# streams_v02_bargraph.net
KiCad netlist of a schematic drawn in EAGLE
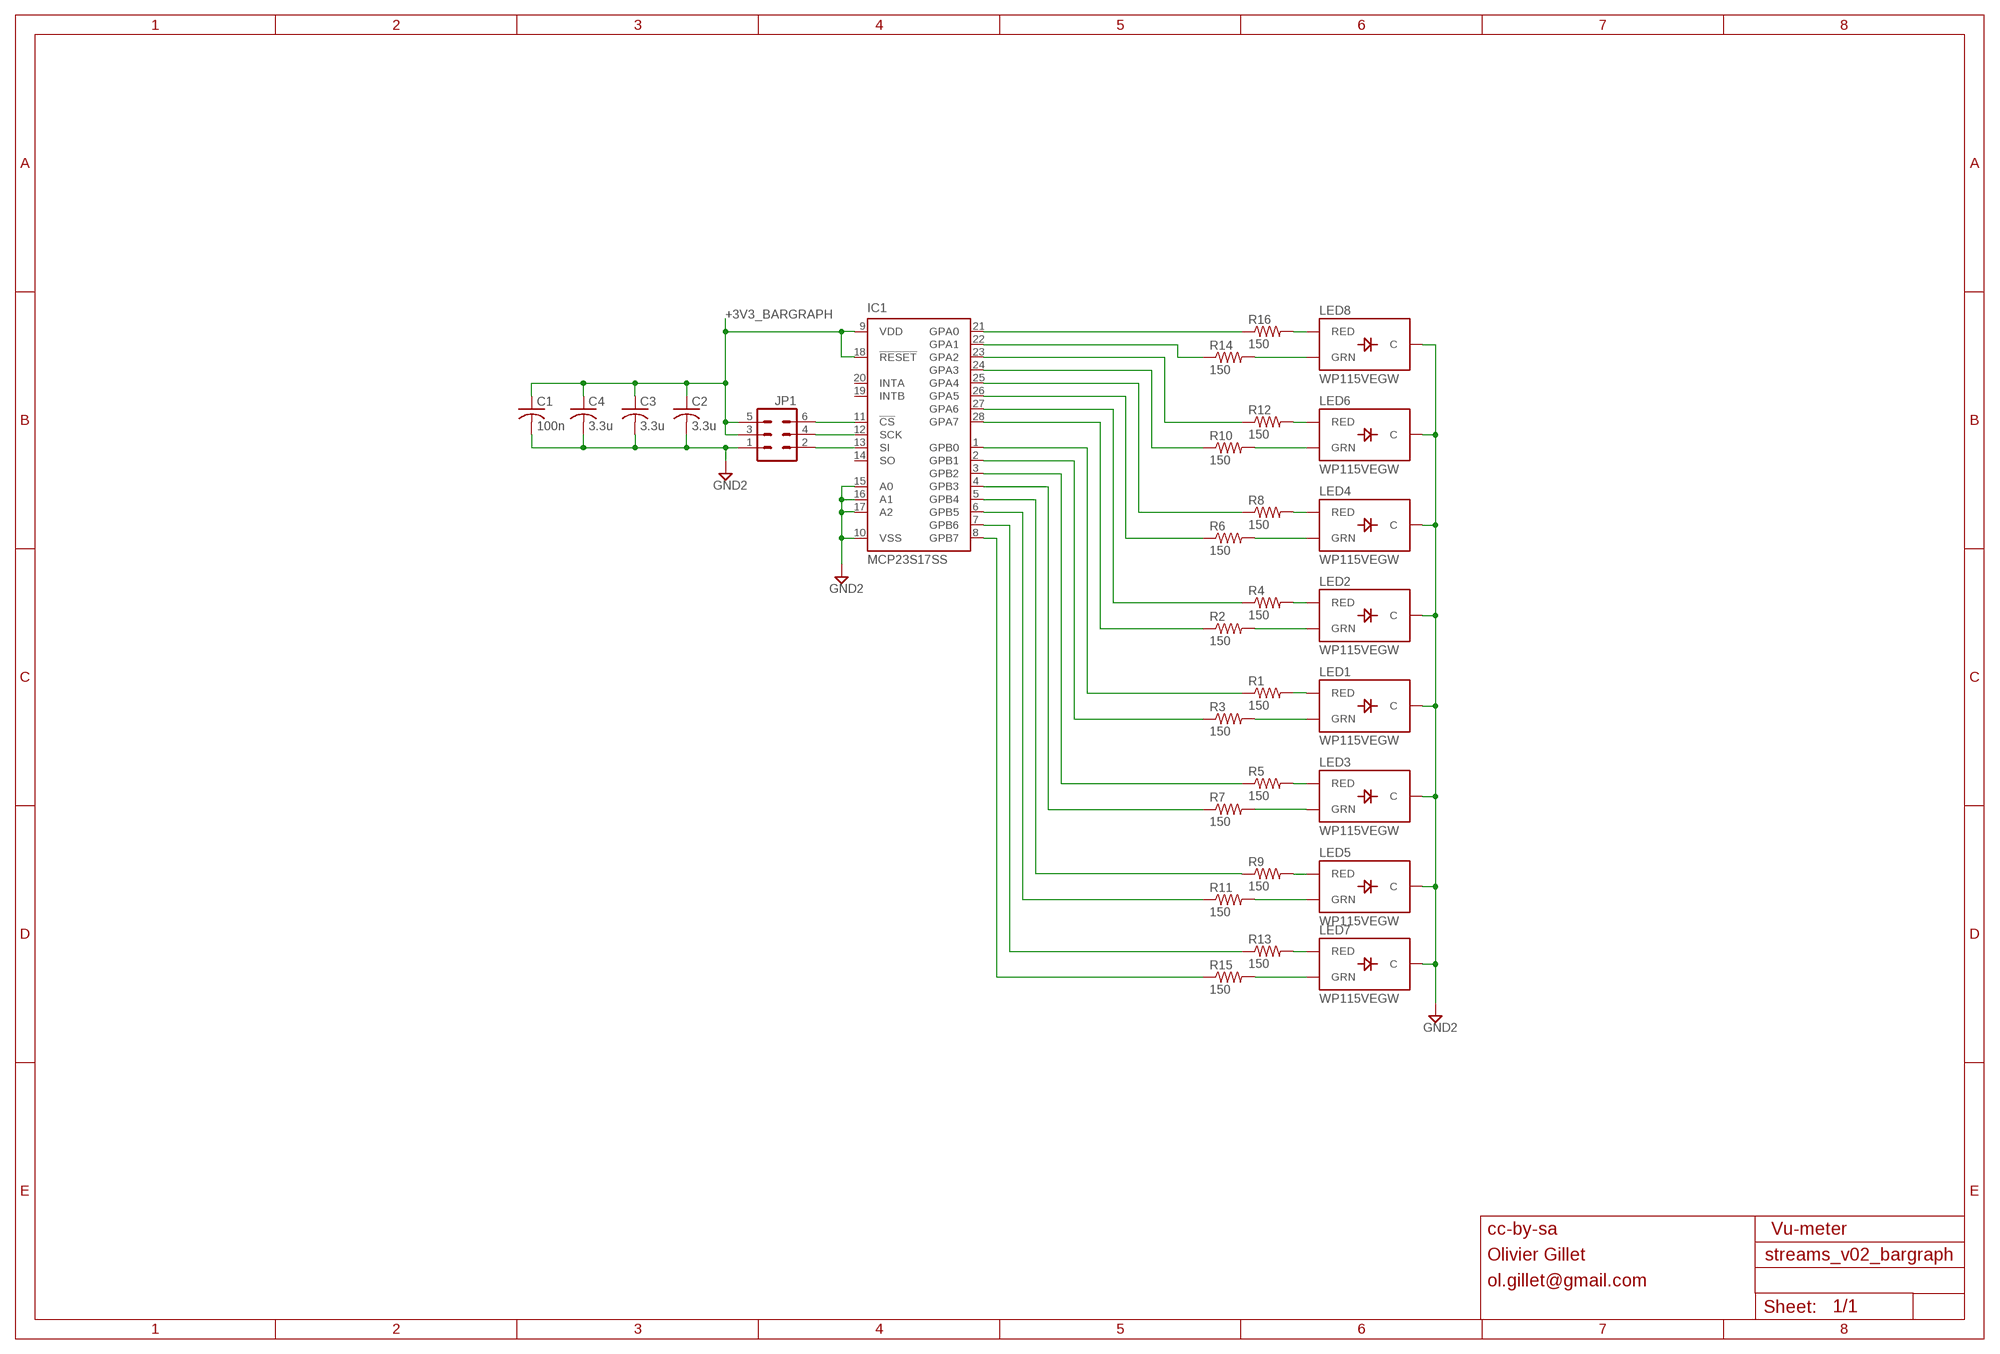
[diagram p0: schematic, sheet 1]

(export (version "E")
  (design (tool "Eeschema 10.0.6"))
  (components
    (comp (ref "C1")
      (value "100n")
      (footprint "eagle-import:C0603")
      (libsource (lib "eagle-import") (part "C-USC0603"))
    )
    (comp (ref "C2")
      (value "3.3u")
      (footprint "eagle-import:C0603")
      (libsource (lib "eagle-import") (part "C-USC0603"))
    )
    (comp (ref "C3")
      (value "3.3u")
      (footprint "eagle-import:C0603")
      (libsource (lib "eagle-import") (part "C-USC0603"))
    )
    (comp (ref "C4")
      (value "3.3u")
      (footprint "eagle-import:C0603")
      (libsource (lib "eagle-import") (part "C-USC0603"))
    )
    (comp (ref "IC1")
      (value "MCP23S17SS")
      (footprint "eagle-import:SSOP28")
      (libsource (lib "eagle-import") (part "MCP23S17SS"))
    )
    (comp (ref "JP1")
      (value "M03X2")
      (footprint "eagle-import:2X3")
      (libsource (lib "eagle-import") (part "M03X2"))
    )
    (comp (ref "LED1")
      (value "WP115VEGW")
      (footprint "eagle-import:LED-BICOLOR-THROUGHHOLE")
      (libsource (lib "eagle-import") (part "LED-BICOLOR-THROUGHHOLE"))
    )
    (comp (ref "LED2")
      (value "WP115VEGW")
      (footprint "eagle-import:LED-BICOLOR-THROUGHHOLE")
      (libsource (lib "eagle-import") (part "LED-BICOLOR-THROUGHHOLE"))
    )
    (comp (ref "LED3")
      (value "WP115VEGW")
      (footprint "eagle-import:LED-BICOLOR-THROUGHHOLE")
      (libsource (lib "eagle-import") (part "LED-BICOLOR-THROUGHHOLE"))
    )
    (comp (ref "LED4")
      (value "WP115VEGW")
      (footprint "eagle-import:LED-BICOLOR-THROUGHHOLE")
      (libsource (lib "eagle-import") (part "LED-BICOLOR-THROUGHHOLE"))
    )
    (comp (ref "LED5")
      (value "WP115VEGW")
      (footprint "eagle-import:LED-BICOLOR-THROUGHHOLE")
      (libsource (lib "eagle-import") (part "LED-BICOLOR-THROUGHHOLE"))
    )
    (comp (ref "LED6")
      (value "WP115VEGW")
      (footprint "eagle-import:LED-BICOLOR-THROUGHHOLE")
      (libsource (lib "eagle-import") (part "LED-BICOLOR-THROUGHHOLE"))
    )
    (comp (ref "LED7")
      (value "WP115VEGW")
      (footprint "eagle-import:LED-BICOLOR-THROUGHHOLE")
      (libsource (lib "eagle-import") (part "LED-BICOLOR-THROUGHHOLE"))
    )
    (comp (ref "LED8")
      (value "WP115VEGW")
      (footprint "eagle-import:LED-BICOLOR-THROUGHHOLE")
      (libsource (lib "eagle-import") (part "LED-BICOLOR-THROUGHHOLE"))
    )
    (comp (ref "R1")
      (value "150")
      (footprint "eagle-import:R0603")
      (libsource (lib "eagle-import") (part "R-US_R0603"))
    )
    (comp (ref "R2")
      (value "150")
      (footprint "eagle-import:R0603")
      (libsource (lib "eagle-import") (part "R-US_R0603"))
    )
    (comp (ref "R3")
      (value "150")
      (footprint "eagle-import:R0603")
      (libsource (lib "eagle-import") (part "R-US_R0603"))
    )
    (comp (ref "R4")
      (value "150")
      (footprint "eagle-import:R0603")
      (libsource (lib "eagle-import") (part "R-US_R0603"))
    )
    (comp (ref "R5")
      (value "150")
      (footprint "eagle-import:R0603")
      (libsource (lib "eagle-import") (part "R-US_R0603"))
    )
    (comp (ref "R6")
      (value "150")
      (footprint "eagle-import:R0603")
      (libsource (lib "eagle-import") (part "R-US_R0603"))
    )
    (comp (ref "R7")
      (value "150")
      (footprint "eagle-import:R0603")
      (libsource (lib "eagle-import") (part "R-US_R0603"))
    )
    (comp (ref "R8")
      (value "150")
      (footprint "eagle-import:R0603")
      (libsource (lib "eagle-import") (part "R-US_R0603"))
    )
    (comp (ref "R9")
      (value "150")
      (footprint "eagle-import:R0603")
      (libsource (lib "eagle-import") (part "R-US_R0603"))
    )
    (comp (ref "R10")
      (value "150")
      (footprint "eagle-import:R0603")
      (libsource (lib "eagle-import") (part "R-US_R0603"))
    )
    (comp (ref "R11")
      (value "150")
      (footprint "eagle-import:R0603")
      (libsource (lib "eagle-import") (part "R-US_R0603"))
    )
    (comp (ref "R12")
      (value "150")
      (footprint "eagle-import:R0603")
      (libsource (lib "eagle-import") (part "R-US_R0603"))
    )
    (comp (ref "R13")
      (value "150")
      (footprint "eagle-import:R0603")
      (libsource (lib "eagle-import") (part "R-US_R0603"))
    )
    (comp (ref "R14")
      (value "150")
      (footprint "eagle-import:R0603")
      (libsource (lib "eagle-import") (part "R-US_R0603"))
    )
    (comp (ref "R15")
      (value "150")
      (footprint "eagle-import:R0603")
      (libsource (lib "eagle-import") (part "R-US_R0603"))
    )
    (comp (ref "R16")
      (value "150")
      (footprint "eagle-import:R0603")
      (libsource (lib "eagle-import") (part "R-US_R0603"))
    )
  )
  (nets
    (net (code "1") (name "/+3V3_BARGRAPH") (class "Default")
      (node (ref "C1") (pin "1") (pinfunction "1_1") (pintype "passive"))
      (node (ref "C2") (pin "1") (pinfunction "1_1") (pintype "passive"))
      (node (ref "C3") (pin "1") (pinfunction "1_1") (pintype "passive"))
      (node (ref "C4") (pin "1") (pinfunction "1_1") (pintype "passive"))
      (node (ref "IC1") (pin "18") (pinfunction "~{RESET}_18") (pintype "input"))
      (node (ref "IC1") (pin "9") (pinfunction "VDD_9") (pintype "power_in"))
      (node (ref "JP1") (pin "3") (pinfunction "3_3") (pintype "passive"))
      (node (ref "JP1") (pin "5") (pinfunction "5_5") (pintype "passive"))
    )
    (net (code "2") (name "GND2") (class "Default")
      (node (ref "C1") (pin "2") (pinfunction "2_2") (pintype "passive"))
      (node (ref "C2") (pin "2") (pinfunction "2_2") (pintype "passive"))
      (node (ref "C3") (pin "2") (pinfunction "2_2") (pintype "passive"))
      (node (ref "C4") (pin "2") (pinfunction "2_2") (pintype "passive"))
      (node (ref "IC1") (pin "10") (pinfunction "VSS_10") (pintype "power_in"))
      (node (ref "IC1") (pin "15") (pinfunction "A0_15") (pintype "input"))
      (node (ref "IC1") (pin "16") (pinfunction "A1_16") (pintype "input"))
      (node (ref "IC1") (pin "17") (pinfunction "A2_17") (pintype "input"))
      (node (ref "JP1") (pin "1") (pinfunction "1_1") (pintype "passive"))
      (node (ref "LED1") (pin "2") (pinfunction "C_2") (pintype "bidirectional"))
      (node (ref "LED2") (pin "2") (pinfunction "C_2") (pintype "bidirectional"))
      (node (ref "LED3") (pin "2") (pinfunction "C_2") (pintype "bidirectional"))
      (node (ref "LED4") (pin "2") (pinfunction "C_2") (pintype "bidirectional"))
      (node (ref "LED5") (pin "2") (pinfunction "C_2") (pintype "bidirectional"))
      (node (ref "LED6") (pin "2") (pinfunction "C_2") (pintype "bidirectional"))
      (node (ref "LED7") (pin "2") (pinfunction "C_2") (pintype "bidirectional"))
      (node (ref "LED8") (pin "2") (pinfunction "C_2") (pintype "bidirectional"))
    )
    (net (code "3") (name "Net-(IC1-GPA0)") (class "Default")
      (node (ref "IC1") (pin "21") (pinfunction "GPA0_21") (pintype "bidirectional"))
      (node (ref "R16") (pin "1") (pinfunction "1_1") (pintype "passive"))
    )
    (net (code "4") (name "Net-(IC1-GPA1)") (class "Default")
      (node (ref "IC1") (pin "22") (pinfunction "GPA1_22") (pintype "bidirectional"))
      (node (ref "R14") (pin "1") (pinfunction "1_1") (pintype "passive"))
    )
    (net (code "5") (name "Net-(IC1-GPA2)") (class "Default")
      (node (ref "IC1") (pin "23") (pinfunction "GPA2_23") (pintype "bidirectional"))
      (node (ref "R12") (pin "1") (pinfunction "1_1") (pintype "passive"))
    )
    (net (code "6") (name "Net-(IC1-GPA3)") (class "Default")
      (node (ref "IC1") (pin "24") (pinfunction "GPA3_24") (pintype "bidirectional"))
      (node (ref "R10") (pin "1") (pinfunction "1_1") (pintype "passive"))
    )
    (net (code "7") (name "Net-(IC1-GPA4)") (class "Default")
      (node (ref "IC1") (pin "25") (pinfunction "GPA4_25") (pintype "bidirectional"))
      (node (ref "R8") (pin "1") (pinfunction "1_1") (pintype "passive"))
    )
    (net (code "8") (name "Net-(IC1-GPA5)") (class "Default")
      (node (ref "IC1") (pin "26") (pinfunction "GPA5_26") (pintype "bidirectional"))
      (node (ref "R6") (pin "1") (pinfunction "1_1") (pintype "passive"))
    )
    (net (code "9") (name "Net-(IC1-GPA6)") (class "Default")
      (node (ref "IC1") (pin "27") (pinfunction "GPA6_27") (pintype "bidirectional"))
      (node (ref "R4") (pin "1") (pinfunction "1_1") (pintype "passive"))
    )
    (net (code "10") (name "Net-(IC1-GPA7)") (class "Default")
      (node (ref "IC1") (pin "28") (pinfunction "GPA7_28") (pintype "bidirectional"))
      (node (ref "R2") (pin "1") (pinfunction "1_1") (pintype "passive"))
    )
    (net (code "11") (name "Net-(IC1-GPB0)") (class "Default")
      (node (ref "IC1") (pin "1") (pinfunction "GPB0_1") (pintype "bidirectional"))
      (node (ref "R1") (pin "1") (pinfunction "1_1") (pintype "passive"))
    )
    (net (code "12") (name "Net-(IC1-GPB1)") (class "Default")
      (node (ref "IC1") (pin "2") (pinfunction "GPB1_2") (pintype "bidirectional"))
      (node (ref "R3") (pin "1") (pinfunction "1_1") (pintype "passive"))
    )
    (net (code "13") (name "Net-(IC1-GPB2)") (class "Default")
      (node (ref "IC1") (pin "3") (pinfunction "GPB2_3") (pintype "bidirectional"))
      (node (ref "R5") (pin "1") (pinfunction "1_1") (pintype "passive"))
    )
    (net (code "14") (name "Net-(IC1-GPB3)") (class "Default")
      (node (ref "IC1") (pin "4") (pinfunction "GPB3_4") (pintype "bidirectional"))
      (node (ref "R7") (pin "1") (pinfunction "1_1") (pintype "passive"))
    )
    (net (code "15") (name "Net-(IC1-GPB4)") (class "Default")
      (node (ref "IC1") (pin "5") (pinfunction "GPB4_5") (pintype "bidirectional"))
      (node (ref "R9") (pin "1") (pinfunction "1_1") (pintype "passive"))
    )
    (net (code "16") (name "Net-(IC1-GPB5)") (class "Default")
      (node (ref "IC1") (pin "6") (pinfunction "GPB5_6") (pintype "bidirectional"))
      (node (ref "R11") (pin "1") (pinfunction "1_1") (pintype "passive"))
    )
    (net (code "17") (name "Net-(IC1-GPB6)") (class "Default")
      (node (ref "IC1") (pin "7") (pinfunction "GPB6_7") (pintype "bidirectional"))
      (node (ref "R13") (pin "1") (pinfunction "1_1") (pintype "passive"))
    )
    (net (code "18") (name "Net-(IC1-GPB7)") (class "Default")
      (node (ref "IC1") (pin "8") (pinfunction "GPB7_8") (pintype "bidirectional"))
      (node (ref "R15") (pin "1") (pinfunction "1_1") (pintype "passive"))
    )
    (net (code "19") (name "Net-(IC1-SCK)") (class "Default")
      (node (ref "IC1") (pin "12") (pinfunction "SCK_12") (pintype "input"))
      (node (ref "JP1") (pin "4") (pinfunction "4_4") (pintype "passive"))
    )
    (net (code "20") (name "Net-(IC1-SI)") (class "Default")
      (node (ref "IC1") (pin "13") (pinfunction "SI_13") (pintype "input"))
      (node (ref "JP1") (pin "2") (pinfunction "2_2") (pintype "passive"))
    )
    (net (code "21") (name "Net-(IC1-~{CS})") (class "Default")
      (node (ref "IC1") (pin "11") (pinfunction "~{CS}_11") (pintype "input"))
      (node (ref "JP1") (pin "6") (pinfunction "6_6") (pintype "passive"))
    )
    (net (code "22") (name "Net-(LED1-GRN)") (class "Default")
      (node (ref "LED1") (pin "1") (pinfunction "GRN_1") (pintype "bidirectional"))
      (node (ref "R3") (pin "2") (pinfunction "2_2") (pintype "passive"))
    )
    (net (code "23") (name "Net-(LED1-RED)") (class "Default")
      (node (ref "LED1") (pin "3") (pinfunction "RED_3") (pintype "bidirectional"))
      (node (ref "R1") (pin "2") (pinfunction "2_2") (pintype "passive"))
    )
    (net (code "24") (name "Net-(LED2-GRN)") (class "Default")
      (node (ref "LED2") (pin "1") (pinfunction "GRN_1") (pintype "bidirectional"))
      (node (ref "R2") (pin "2") (pinfunction "2_2") (pintype "passive"))
    )
    (net (code "25") (name "Net-(LED2-RED)") (class "Default")
      (node (ref "LED2") (pin "3") (pinfunction "RED_3") (pintype "bidirectional"))
      (node (ref "R4") (pin "2") (pinfunction "2_2") (pintype "passive"))
    )
    (net (code "26") (name "Net-(LED3-GRN)") (class "Default")
      (node (ref "LED3") (pin "1") (pinfunction "GRN_1") (pintype "bidirectional"))
      (node (ref "R7") (pin "2") (pinfunction "2_2") (pintype "passive"))
    )
    (net (code "27") (name "Net-(LED3-RED)") (class "Default")
      (node (ref "LED3") (pin "3") (pinfunction "RED_3") (pintype "bidirectional"))
      (node (ref "R5") (pin "2") (pinfunction "2_2") (pintype "passive"))
    )
    (net (code "28") (name "Net-(LED4-GRN)") (class "Default")
      (node (ref "LED4") (pin "1") (pinfunction "GRN_1") (pintype "bidirectional"))
      (node (ref "R6") (pin "2") (pinfunction "2_2") (pintype "passive"))
    )
    (net (code "29") (name "Net-(LED4-RED)") (class "Default")
      (node (ref "LED4") (pin "3") (pinfunction "RED_3") (pintype "bidirectional"))
      (node (ref "R8") (pin "2") (pinfunction "2_2") (pintype "passive"))
    )
    (net (code "30") (name "Net-(LED5-GRN)") (class "Default")
      (node (ref "LED5") (pin "1") (pinfunction "GRN_1") (pintype "bidirectional"))
      (node (ref "R11") (pin "2") (pinfunction "2_2") (pintype "passive"))
    )
    (net (code "31") (name "Net-(LED5-RED)") (class "Default")
      (node (ref "LED5") (pin "3") (pinfunction "RED_3") (pintype "bidirectional"))
      (node (ref "R9") (pin "2") (pinfunction "2_2") (pintype "passive"))
    )
    (net (code "32") (name "Net-(LED6-GRN)") (class "Default")
      (node (ref "LED6") (pin "1") (pinfunction "GRN_1") (pintype "bidirectional"))
      (node (ref "R10") (pin "2") (pinfunction "2_2") (pintype "passive"))
    )
    (net (code "33") (name "Net-(LED6-RED)") (class "Default")
      (node (ref "LED6") (pin "3") (pinfunction "RED_3") (pintype "bidirectional"))
      (node (ref "R12") (pin "2") (pinfunction "2_2") (pintype "passive"))
    )
    (net (code "34") (name "Net-(LED7-GRN)") (class "Default")
      (node (ref "LED7") (pin "1") (pinfunction "GRN_1") (pintype "bidirectional"))
      (node (ref "R15") (pin "2") (pinfunction "2_2") (pintype "passive"))
    )
    (net (code "35") (name "Net-(LED7-RED)") (class "Default")
      (node (ref "LED7") (pin "3") (pinfunction "RED_3") (pintype "bidirectional"))
      (node (ref "R13") (pin "2") (pinfunction "2_2") (pintype "passive"))
    )
    (net (code "36") (name "Net-(LED8-GRN)") (class "Default")
      (node (ref "LED8") (pin "1") (pinfunction "GRN_1") (pintype "bidirectional"))
      (node (ref "R14") (pin "2") (pinfunction "2_2") (pintype "passive"))
    )
    (net (code "37") (name "Net-(LED8-RED)") (class "Default")
      (node (ref "LED8") (pin "3") (pinfunction "RED_3") (pintype "bidirectional"))
      (node (ref "R16") (pin "2") (pinfunction "2_2") (pintype "passive"))
    )
    (net (code "38") (name "unconnected-(IC1-INTA-Pad20)") (class "Default")
      (node (ref "IC1") (pin "20") (pinfunction "INTA_20") (pintype "output"))
    )
    (net (code "39") (name "unconnected-(IC1-INTB-Pad19)") (class "Default")
      (node (ref "IC1") (pin "19") (pinfunction "INTB_19") (pintype "output"))
    )
    (net (code "40") (name "unconnected-(IC1-SO-Pad14)") (class "Default")
      (node (ref "IC1") (pin "14") (pinfunction "SO_14") (pintype "output"))
    )
  )
)
